# Sheet1.net
KiCad netlist of a schematic drawn in Altium Designer
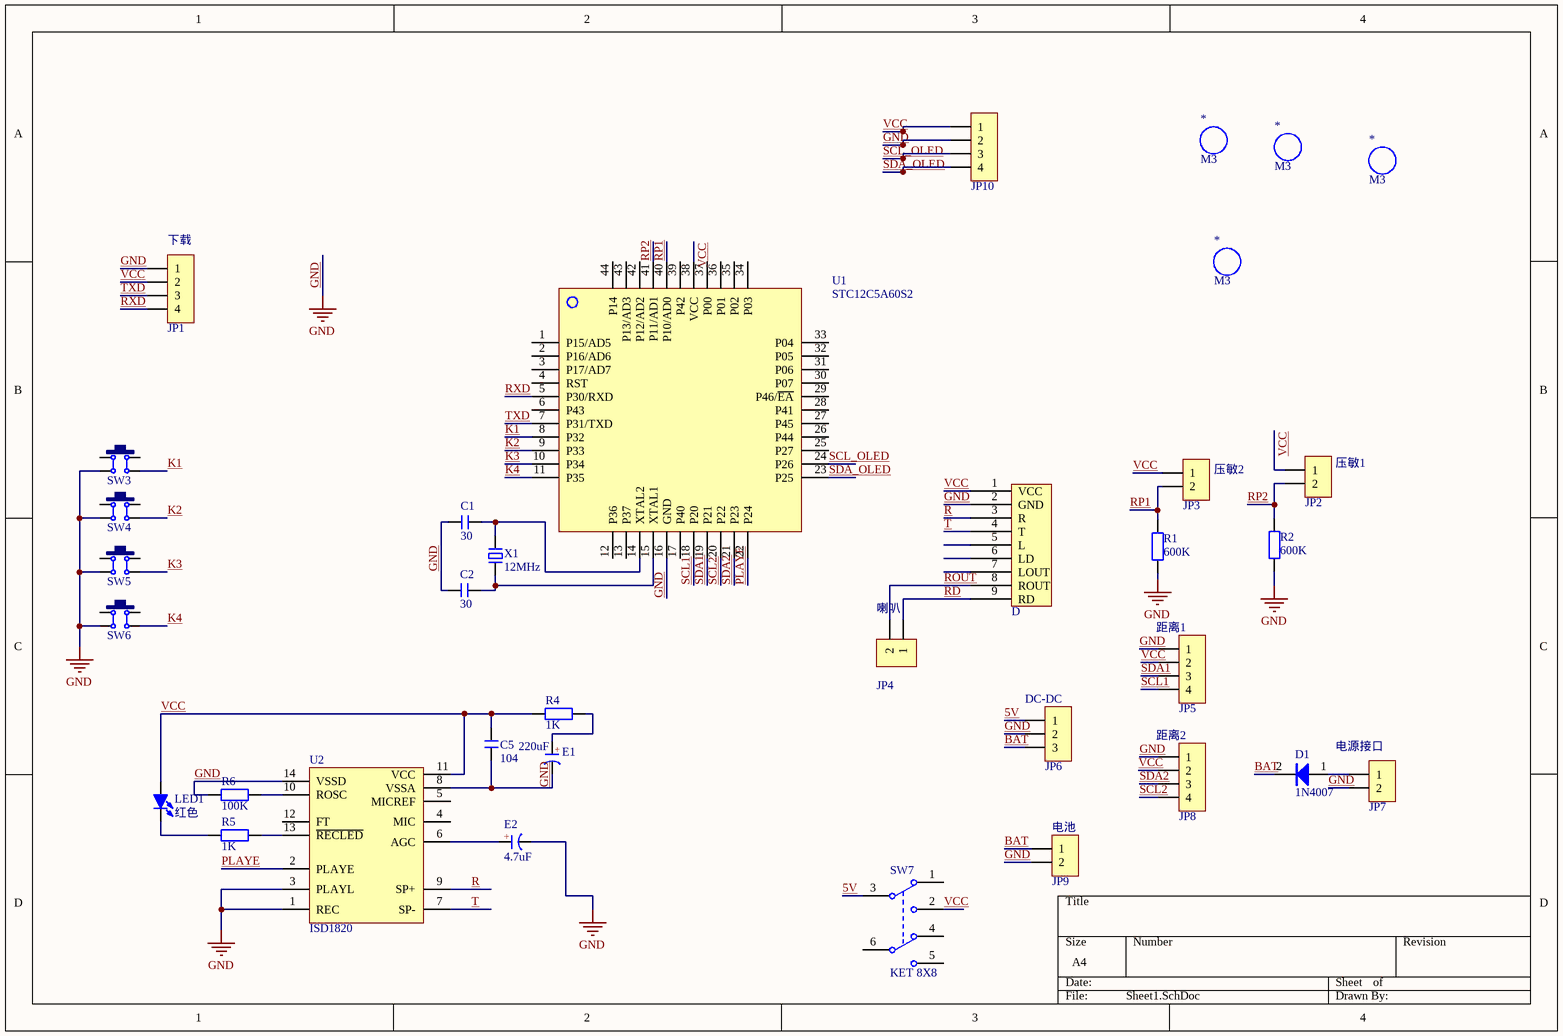
[diagram p0: Sheet1.SchDoc]

(export (version "E")
  (design (tool "Eeschema 10.0.6"))
  (components
    (comp (ref "C1")
      (value "30")
      (footprint "C0805")
      (description "无极性贴片电容")
      (libsource (lib "Mylite") (part "C"))
    )
    (comp (ref "C2")
      (value "30")
      (footprint "C0805")
      (description "无极性贴片电容")
      (libsource (lib "Mylite") (part "C"))
    )
    (comp (ref "C5")
      (value "104")
      (footprint "C0805")
      (description "无极性贴片电容")
      (libsource (lib "Mylite") (part "C"))
    )
    (comp (ref "D") (value "功放模块") (footprint "功放模块") (libsource (lib "Mylite") (part "功放模块")))
    (comp (ref "D1")
      (value "1N4007")
      (footprint "SOD-123")
      (description "整流二极管")
      (libsource (lib "Mylite") (part "1N4007"))
    )
    (comp (ref "E1")
      (value "220uF")
      (footprint "CAP 1.5*4*8")
      (description "直插电解电容")
      (libsource (lib "Mylite") (part "C-CAP"))
    )
    (comp (ref "E2")
      (value "4.7uF")
      (footprint "CAP 1.5*4*8")
      (description "直插电解电容")
      (libsource (lib "") (part "C-CAP_1"))
    )
    (comp (ref "JP1")
      (value "下载")
      (footprint "HDR2.54-LI-4P")
      (description "4P接插件")
      (libsource (lib "Mylite") (part "Header 4"))
    )
    (comp (ref "JP2")
      (value "压敏1")
      (footprint "XH2.54-WI-2P")
      (description "2P接插件")
      (libsource (lib "Mylite") (part "Header 2"))
    )
    (comp (ref "JP3")
      (value "压敏2")
      (footprint "XH2.54-WI-2P")
      (description "2P接插件")
      (libsource (lib "Mylite") (part "Header 2"))
    )
    (comp (ref "JP4")
      (value "喇叭")
      (footprint "HDR2.54-LI-2P")
      (description "2P接插件")
      (libsource (lib "") (part "Header 2_1"))
    )
    (comp (ref "JP5")
      (value "距离1")
      (footprint "XH2.54-WI-4P")
      (description "4P接插件")
      (libsource (lib "Mylite") (part "Header 4"))
    )
    (comp (ref "JP6")
      (value "DC-DC")
      (footprint "HDR2.54-LI-3P")
      (description "3P接插件")
      (libsource (lib "Mylite") (part "Header 3"))
    )
    (comp (ref "JP7")
      (value "电源接口")
      (footprint "KF301-2P-BLUE")
      (description "2P接插件")
      (libsource (lib "Mylite") (part "Header 2"))
    )
    (comp (ref "JP8")
      (value "距离2")
      (footprint "XH2.54-WI-4P")
      (description "4P接插件")
      (libsource (lib "Mylite") (part "Header 4"))
    )
    (comp (ref "JP9")
      (value "电池")
      (footprint "HDR2.54-LI-2P")
      (description "2P接插件")
      (libsource (lib "Mylite") (part "Header 2"))
    )
    (comp (ref "JP10")
      (value "HDR-1X4")
      (footprint "HDR2.54-M-LI-4P")
      (description "4P接插件")
      (libsource (lib "Mylite") (part "Header 4"))
    )
    (comp (ref "LED1")
      (value "红色")
      (footprint "LED 0805G")
      (description "贴片LED")
      (libsource (lib "Mylite") (part "LED-SMD"))
    )
    (comp (ref "R1")
      (value "600K")
      (footprint "R0805")
      (description "Resistor")
      (fields (field (name "PUBLISHER") "Altium Limited"))
      (libsource (lib "") (part "Resistor_1"))
    )
    (comp (ref "R2")
      (value "600K")
      (footprint "R0805")
      (description "Resistor")
      (fields (field (name "PUBLISHER") "Altium Limited"))
      (libsource (lib "") (part "Resistor_1"))
    )
    (comp (ref "R4")
      (value "1K")
      (footprint "R0805")
      (description "Resistor")
      (fields (field (name "PUBLISHER") "Altium Limited"))
      (libsource (lib "Mylite") (part "Resistor"))
    )
    (comp (ref "R5")
      (value "1K")
      (footprint "R0805")
      (description "Resistor")
      (fields (field (name "PUBLISHER") "Altium Limited"))
      (libsource (lib "Mylite") (part "Resistor"))
    )
    (comp (ref "R6")
      (value "100K")
      (footprint "R0805")
      (description "Resistor")
      (fields (field (name "PUBLISHER") "Altium Limited"))
      (libsource (lib "Mylite") (part "Resistor"))
    )
    (comp (ref "SW3")
      (value "6x6x5")
      (footprint "TSW DIP-6*6*6")
      (description "直插6x6轻触开关")
      (libsource (lib "Mylite") (part "TSW DIP-6x6"))
    )
    (comp (ref "SW4")
      (value "6x6x5")
      (footprint "TSW DIP-6*6*6")
      (description "直插6x6轻触开关")
      (libsource (lib "Mylite") (part "TSW DIP-6x6"))
    )
    (comp (ref "SW5")
      (value "6x6x5")
      (footprint "TSW DIP-6*6*6")
      (description "直插6x6轻触开关")
      (libsource (lib "Mylite") (part "TSW DIP-6x6"))
    )
    (comp (ref "SW6")
      (value "6x6x5")
      (footprint "TSW DIP-6*6*6")
      (description "直插6x6轻触开关")
      (libsource (lib "Mylite") (part "TSW DIP-6x6"))
    )
    (comp (ref "SW7")
      (value "KET 8X8")
      (footprint "KFT DIP-8X8")
      (description "8*8自锁开关")
      (libsource (lib "Mylite") (part "KET 8X8"))
    )
    (comp (ref "U1")
      (value "STC12C5A60S2")
      (footprint "TQFP44 10x10_N")
      (description "STC单片机")
      (libsource (lib "Mylite") (part "STC12C5A60S2"))
    )
    (comp (ref "U2")
      (value "ISD1820")
      (footprint "DIP14")
      (description "录音模块")
      (libsource (lib "Mylite") (part "ISD1820"))
    )
    (comp (ref "X1")
      (value "12MHz")
      (footprint "OSC HC-49SMD")
      (description "2脚无源脚晶振")
      (libsource (lib "Mylite") (part "XTAL-2P"))
    )
  )
  (nets
    (net (code "1") (name "/5V") (class "Default")
      (node (ref "JP6") (pin "1") (pinfunction "1_1") (pintype "passive"))
      (node (ref "SW7") (pin "3") (pinfunction "NO1_3") (pintype "passive"))
    )
    (net (code "2") (name "/BAT") (class "Default")
      (node (ref "D1") (pin "2") (pinfunction "K_2") (pintype "passive"))
      (node (ref "JP6") (pin "3") (pinfunction "3_3") (pintype "passive"))
      (node (ref "JP9") (pin "1") (pinfunction "1_1") (pintype "passive"))
    )
    (net (code "3") (name "/K1") (class "Default")
      (node (ref "SW3") (pin "3") (pinfunction "3_3") (pintype "passive"))
      (node (ref "U1") (pin "8") (pinfunction "P32_8") (pintype "passive"))
    )
    (net (code "4") (name "/K2") (class "Default")
      (node (ref "SW4") (pin "3") (pinfunction "3_3") (pintype "passive"))
      (node (ref "U1") (pin "9") (pinfunction "P33_9") (pintype "passive"))
    )
    (net (code "5") (name "/K3") (class "Default")
      (node (ref "SW5") (pin "3") (pinfunction "3_3") (pintype "passive"))
      (node (ref "U1") (pin "10") (pinfunction "P34_10") (pintype "passive"))
    )
    (net (code "6") (name "/K4") (class "Default")
      (node (ref "SW6") (pin "3") (pinfunction "3_3") (pintype "passive"))
      (node (ref "U1") (pin "11") (pinfunction "P35_11") (pintype "passive"))
    )
    (net (code "7") (name "/PLAYE") (class "Default")
      (node (ref "U1") (pin "22") (pinfunction "P24_22") (pintype "passive"))
      (node (ref "U2") (pin "2") (pinfunction "PLAYE_2") (pintype "passive"))
    )
    (net (code "8") (name "/R") (class "Default")
      (node (ref "D") (pin "3") (pinfunction "R_3") (pintype "passive"))
      (node (ref "U2") (pin "9") (pinfunction "SP+_9") (pintype "passive"))
    )
    (net (code "9") (name "/RD") (class "Default")
      (node (ref "D") (pin "9") (pinfunction "RD_9") (pintype "passive"))
      (node (ref "JP4") (pin "1") (pinfunction "1_1") (pintype "passive"))
    )
    (net (code "10") (name "/ROUT") (class "Default")
      (node (ref "D") (pin "8") (pinfunction "ROUT_8") (pintype "passive"))
      (node (ref "JP4") (pin "2") (pinfunction "2_2") (pintype "passive"))
    )
    (net (code "11") (name "/RP1") (class "Default")
      (node (ref "JP3") (pin "2") (pinfunction "2_2") (pintype "passive"))
      (node (ref "R1") (pin "2") (pinfunction "2_2") (pintype "passive"))
      (node (ref "U1") (pin "40") (pinfunction "P10/AD0_40") (pintype "passive"))
    )
    (net (code "12") (name "/RP2") (class "Default")
      (node (ref "JP2") (pin "2") (pinfunction "2_2") (pintype "passive"))
      (node (ref "R2") (pin "2") (pinfunction "2_2") (pintype "passive"))
      (node (ref "U1") (pin "41") (pinfunction "P11/AD1_41") (pintype "passive"))
    )
    (net (code "13") (name "/RXD") (class "Default")
      (node (ref "JP1") (pin "4") (pinfunction "4_4") (pintype "passive"))
      (node (ref "U1") (pin "5") (pinfunction "P30/RXD_5") (pintype "passive"))
    )
    (net (code "14") (name "/SCL1") (class "Default")
      (node (ref "JP5") (pin "4") (pinfunction "4_4") (pintype "passive"))
      (node (ref "U1") (pin "18") (pinfunction "P20_18") (pintype "passive"))
    )
    (net (code "15") (name "/SCL2") (class "Default")
      (node (ref "JP8") (pin "4") (pinfunction "4_4") (pintype "passive"))
      (node (ref "U1") (pin "20") (pinfunction "P22_20") (pintype "passive"))
    )
    (net (code "16") (name "/SCL_OLED") (class "Default")
      (node (ref "JP10") (pin "3") (pinfunction "3_3") (pintype "passive"))
      (node (ref "U1") (pin "24") (pinfunction "P26_24") (pintype "passive"))
    )
    (net (code "17") (name "/SDA1") (class "Default")
      (node (ref "JP5") (pin "3") (pinfunction "3_3") (pintype "passive"))
      (node (ref "U1") (pin "19") (pinfunction "P21_19") (pintype "passive"))
    )
    (net (code "18") (name "/SDA2") (class "Default")
      (node (ref "JP8") (pin "3") (pinfunction "3_3") (pintype "passive"))
      (node (ref "U1") (pin "21") (pinfunction "P23_21") (pintype "passive"))
    )
    (net (code "19") (name "/SDA_OLED") (class "Default")
      (node (ref "JP10") (pin "4") (pinfunction "4_4") (pintype "passive"))
      (node (ref "U1") (pin "23") (pinfunction "P25_23") (pintype "passive"))
    )
    (net (code "20") (name "/T") (class "Default")
      (node (ref "D") (pin "4") (pinfunction "T_4") (pintype "passive"))
      (node (ref "U2") (pin "7") (pinfunction "SP-_7") (pintype "passive"))
    )
    (net (code "21") (name "/TXD") (class "Default")
      (node (ref "JP1") (pin "3") (pinfunction "3_3") (pintype "passive"))
      (node (ref "U1") (pin "7") (pinfunction "P31/TXD_7") (pintype "passive"))
    )
    (net (code "22") (name "/VCC") (class "Default")
      (node (ref "C5") (pin "2") (pinfunction "2_2") (pintype "passive"))
      (node (ref "D") (pin "1") (pinfunction "VCC_1") (pintype "passive"))
      (node (ref "JP1") (pin "2") (pinfunction "2_2") (pintype "passive"))
      (node (ref "JP10") (pin "1") (pinfunction "1_1") (pintype "passive"))
      (node (ref "JP2") (pin "1") (pinfunction "1_1") (pintype "passive"))
      (node (ref "JP3") (pin "1") (pinfunction "1_1") (pintype "passive"))
      (node (ref "JP5") (pin "2") (pinfunction "2_2") (pintype "passive"))
      (node (ref "JP8") (pin "2") (pinfunction "2_2") (pintype "passive"))
      (node (ref "LED1") (pin "1") (pinfunction "A_1") (pintype "passive"))
      (node (ref "R4") (pin "1") (pinfunction "1_1") (pintype "passive"))
      (node (ref "SW7") (pin "2") (pinfunction "COM2_2") (pintype "passive"))
      (node (ref "U1") (pin "38") (pinfunction "VCC_38") (pintype "passive"))
      (node (ref "U2") (pin "11") (pinfunction "VCC_11") (pintype "passive"))
    )
    (net (code "23") (name "GND") (class "Default")
      (node (ref "C1") (pin "2") (pinfunction "2_2") (pintype "passive"))
      (node (ref "C2") (pin "2") (pinfunction "2_2") (pintype "passive"))
      (node (ref "C5") (pin "1") (pinfunction "1_1") (pintype "passive"))
      (node (ref "D") (pin "2") (pinfunction "GND_2") (pintype "passive"))
      (node (ref "E1") (pin "2") (pinfunction "K_2") (pintype "passive"))
      (node (ref "E2") (pin "2") (pinfunction "K_2") (pintype "passive"))
      (node (ref "JP1") (pin "1") (pinfunction "1_1") (pintype "passive"))
      (node (ref "JP10") (pin "2") (pinfunction "2_2") (pintype "passive"))
      (node (ref "JP5") (pin "1") (pinfunction "1_1") (pintype "passive"))
      (node (ref "JP6") (pin "2") (pinfunction "2_2") (pintype "passive"))
      (node (ref "JP7") (pin "2") (pinfunction "2_2") (pintype "passive"))
      (node (ref "JP8") (pin "1") (pinfunction "1_1") (pintype "passive"))
      (node (ref "JP9") (pin "2") (pinfunction "2_2") (pintype "passive"))
      (node (ref "R1") (pin "1") (pinfunction "1_1") (pintype "passive"))
      (node (ref "R2") (pin "1") (pinfunction "1_1") (pintype "passive"))
      (node (ref "R6") (pin "1") (pinfunction "1_1") (pintype "passive"))
      (node (ref "SW3") (pin "4") (pinfunction "4_4") (pintype "passive"))
      (node (ref "SW4") (pin "4") (pinfunction "4_4") (pintype "passive"))
      (node (ref "SW5") (pin "4") (pinfunction "4_4") (pintype "passive"))
      (node (ref "SW6") (pin "4") (pinfunction "4_4") (pintype "passive"))
      (node (ref "U1") (pin "16") (pinfunction "GND_16") (pintype "passive"))
      (node (ref "U2") (pin "1") (pinfunction "REC_1") (pintype "passive"))
      (node (ref "U2") (pin "14") (pinfunction "VSSD_14") (pintype "passive"))
      (node (ref "U2") (pin "3") (pinfunction "PLAYL_3") (pintype "passive"))
      (node (ref "U2") (pin "8") (pinfunction "VSSA_8") (pintype "passive"))
    )
    (net (code "24") (name "Net-(D1-A)") (class "Default")
      (node (ref "D1") (pin "1") (pinfunction "A_1") (pintype "passive"))
      (node (ref "JP7") (pin "1") (pinfunction "1_1") (pintype "passive"))
    )
    (net (code "25") (name "Net-(E1-A)") (class "Default")
      (node (ref "E1") (pin "1") (pinfunction "A_1") (pintype "passive"))
      (node (ref "R4") (pin "2") (pinfunction "2_2") (pintype "passive"))
    )
    (net (code "26") (name "Net-(E2-A)") (class "Default")
      (node (ref "E2") (pin "1") (pinfunction "A_1") (pintype "passive"))
      (node (ref "U2") (pin "6") (pinfunction "AGC_6") (pintype "passive"))
    )
    (net (code "27") (name "Net-(LED1-K)") (class "Default")
      (node (ref "LED1") (pin "2") (pinfunction "K_2") (pintype "passive"))
      (node (ref "R5") (pin "1") (pinfunction "1_1") (pintype "passive"))
    )
    (net (code "28") (name "Net-(U1-XTAL1)") (class "Default")
      (node (ref "C2") (pin "1") (pinfunction "1_1") (pintype "passive"))
      (node (ref "U1") (pin "15") (pinfunction "XTAL1_15") (pintype "passive"))
      (node (ref "X1") (pin "1") (pinfunction "1_1") (pintype "passive"))
    )
    (net (code "29") (name "Net-(U1-XTAL2)") (class "Default")
      (node (ref "C1") (pin "1") (pinfunction "1_1") (pintype "passive"))
      (node (ref "U1") (pin "14") (pinfunction "XTAL2_14") (pintype "passive"))
      (node (ref "X1") (pin "2") (pinfunction "2_2") (pintype "passive"))
    )
    (net (code "30") (name "Net-(U2-ROSC)") (class "Default")
      (node (ref "R6") (pin "2") (pinfunction "2_2") (pintype "passive"))
      (node (ref "U2") (pin "10") (pinfunction "ROSC_10") (pintype "passive"))
    )
    (net (code "31") (name "Net-(U2-~{RECLED})") (class "Default")
      (node (ref "R5") (pin "2") (pinfunction "2_2") (pintype "passive"))
      (node (ref "U2") (pin "13") (pinfunction "~{RECLED}_13") (pintype "passive"))
    )
    (net (code "32") (name "unconnected-(D-L-Pad5)") (class "Default")
      (node (ref "D") (pin "5") (pinfunction "L_5") (pintype "passive"))
    )
    (net (code "33") (name "unconnected-(D-LD-Pad6)") (class "Default")
      (node (ref "D") (pin "6") (pinfunction "LD_6") (pintype "passive"))
    )
    (net (code "34") (name "unconnected-(D-LOUT-Pad7)") (class "Default")
      (node (ref "D") (pin "7") (pinfunction "LOUT_7") (pintype "passive"))
    )
    (net (code "35") (name "unconnected-(SW3-Pad1)") (class "Default")
      (node (ref "SW3") (pin "1") (pinfunction "1_1") (pintype "passive"))
    )
    (net (code "36") (name "unconnected-(SW3-Pad2)") (class "Default")
      (node (ref "SW3") (pin "2") (pinfunction "2_2") (pintype "passive"))
    )
    (net (code "37") (name "unconnected-(SW4-Pad1)") (class "Default")
      (node (ref "SW4") (pin "1") (pinfunction "1_1") (pintype "passive"))
    )
    (net (code "38") (name "unconnected-(SW4-Pad2)") (class "Default")
      (node (ref "SW4") (pin "2") (pinfunction "2_2") (pintype "passive"))
    )
    (net (code "39") (name "unconnected-(SW5-Pad1)") (class "Default")
      (node (ref "SW5") (pin "1") (pinfunction "1_1") (pintype "passive"))
    )
    (net (code "40") (name "unconnected-(SW5-Pad2)") (class "Default")
      (node (ref "SW5") (pin "2") (pinfunction "2_2") (pintype "passive"))
    )
    (net (code "41") (name "unconnected-(SW6-Pad1)") (class "Default")
      (node (ref "SW6") (pin "1") (pinfunction "1_1") (pintype "passive"))
    )
    (net (code "42") (name "unconnected-(SW6-Pad2)") (class "Default")
      (node (ref "SW6") (pin "2") (pinfunction "2_2") (pintype "passive"))
    )
    (net (code "43") (name "unconnected-(SW7-COM2-Pad5)") (class "Default")
      (node (ref "SW7") (pin "5") (pinfunction "COM2_5") (pintype "passive"))
    )
    (net (code "44") (name "unconnected-(SW7-NC1-Pad1)") (class "Default")
      (node (ref "SW7") (pin "1") (pinfunction "NC1_1") (pintype "passive"))
    )
    (net (code "45") (name "unconnected-(SW7-NC2-Pad6)") (class "Default")
      (node (ref "SW7") (pin "6") (pinfunction "NC2_6") (pintype "passive"))
    )
    (net (code "46") (name "unconnected-(SW7-NO2-Pad4)") (class "Default")
      (node (ref "SW7") (pin "4") (pinfunction "NO2_4") (pintype "passive"))
    )
    (net (code "47") (name "unconnected-(U1-P00-Pad37)") (class "Default")
      (node (ref "U1") (pin "37") (pinfunction "P00_37") (pintype "passive"))
    )
    (net (code "48") (name "unconnected-(U1-P01-Pad36)") (class "Default")
      (node (ref "U1") (pin "36") (pinfunction "P01_36") (pintype "passive"))
    )
    (net (code "49") (name "unconnected-(U1-P02-Pad35)") (class "Default")
      (node (ref "U1") (pin "35") (pinfunction "P02_35") (pintype "passive"))
    )
    (net (code "50") (name "unconnected-(U1-P03-Pad34)") (class "Default")
      (node (ref "U1") (pin "34") (pinfunction "P03_34") (pintype "passive"))
    )
    (net (code "51") (name "unconnected-(U1-P04-Pad33)") (class "Default")
      (node (ref "U1") (pin "33") (pinfunction "P04_33") (pintype "passive"))
    )
    (net (code "52") (name "unconnected-(U1-P05-Pad32)") (class "Default")
      (node (ref "U1") (pin "32") (pinfunction "P05_32") (pintype "passive"))
    )
    (net (code "53") (name "unconnected-(U1-P06-Pad31)") (class "Default")
      (node (ref "U1") (pin "31") (pinfunction "P06_31") (pintype "passive"))
    )
    (net (code "54") (name "unconnected-(U1-P07-Pad30)") (class "Default")
      (node (ref "U1") (pin "30") (pinfunction "P07_30") (pintype "passive"))
    )
    (net (code "55") (name "unconnected-(U1-P12{slash}AD2-Pad42)") (class "Default")
      (node (ref "U1") (pin "42") (pinfunction "P12/AD2_42") (pintype "passive"))
    )
    (net (code "56") (name "unconnected-(U1-P13{slash}AD3-Pad43)") (class "Default")
      (node (ref "U1") (pin "43") (pinfunction "P13/AD3_43") (pintype "passive"))
    )
    (net (code "57") (name "unconnected-(U1-P14-Pad44)") (class "Default")
      (node (ref "U1") (pin "44") (pinfunction "P14_44") (pintype "passive"))
    )
    (net (code "58") (name "unconnected-(U1-P15{slash}AD5-Pad1)") (class "Default")
      (node (ref "U1") (pin "1") (pinfunction "P15/AD5_1") (pintype "passive"))
    )
    (net (code "59") (name "unconnected-(U1-P16{slash}AD6-Pad2)") (class "Default")
      (node (ref "U1") (pin "2") (pinfunction "P16/AD6_2") (pintype "passive"))
    )
    (net (code "60") (name "unconnected-(U1-P17{slash}AD7-Pad3)") (class "Default")
      (node (ref "U1") (pin "3") (pinfunction "P17/AD7_3") (pintype "passive"))
    )
    (net (code "61") (name "unconnected-(U1-P27-Pad25)") (class "Default")
      (node (ref "U1") (pin "25") (pinfunction "P27_25") (pintype "passive"))
    )
    (net (code "62") (name "unconnected-(U1-P36-Pad12)") (class "Default")
      (node (ref "U1") (pin "12") (pinfunction "P36_12") (pintype "passive"))
    )
    (net (code "63") (name "unconnected-(U1-P37-Pad13)") (class "Default")
      (node (ref "U1") (pin "13") (pinfunction "P37_13") (pintype "passive"))
    )
    (net (code "64") (name "unconnected-(U1-P40-Pad17)") (class "Default")
      (node (ref "U1") (pin "17") (pinfunction "P40_17") (pintype "passive"))
    )
    (net (code "65") (name "unconnected-(U1-P41-Pad28)") (class "Default")
      (node (ref "U1") (pin "28") (pinfunction "P41_28") (pintype "passive"))
    )
    (net (code "66") (name "unconnected-(U1-P42-Pad39)") (class "Default")
      (node (ref "U1") (pin "39") (pinfunction "P42_39") (pintype "passive"))
    )
    (net (code "67") (name "unconnected-(U1-P43-Pad6)") (class "Default")
      (node (ref "U1") (pin "6") (pinfunction "P43_6") (pintype "passive"))
    )
    (net (code "68") (name "unconnected-(U1-P44-Pad26)") (class "Default")
      (node (ref "U1") (pin "26") (pinfunction "P44_26") (pintype "passive"))
    )
    (net (code "69") (name "unconnected-(U1-P45-Pad27)") (class "Default")
      (node (ref "U1") (pin "27") (pinfunction "P45_27") (pintype "passive"))
    )
    (net (code "70") (name "unconnected-(U1-P46{slash}~{EA}-Pad29)") (class "Default")
      (node (ref "U1") (pin "29") (pinfunction "P46/~{EA}_29") (pintype "passive"))
    )
    (net (code "71") (name "unconnected-(U1-RST-Pad4)") (class "Default")
      (node (ref "U1") (pin "4") (pinfunction "RST_4") (pintype "passive"))
    )
    (net (code "72") (name "unconnected-(U2-FT-Pad12)") (class "Default")
      (node (ref "U2") (pin "12") (pinfunction "FT_12") (pintype "passive"))
    )
    (net (code "73") (name "unconnected-(U2-MIC-Pad4)") (class "Default")
      (node (ref "U2") (pin "4") (pinfunction "MIC_4") (pintype "passive"))
    )
    (net (code "74") (name "unconnected-(U2-MICREF-Pad5)") (class "Default")
      (node (ref "U2") (pin "5") (pinfunction "MICREF_5") (pintype "passive"))
    )
  )
)
